# flowerfriend_rev1.net
KiCad netlist of a schematic drawn in EAGLE
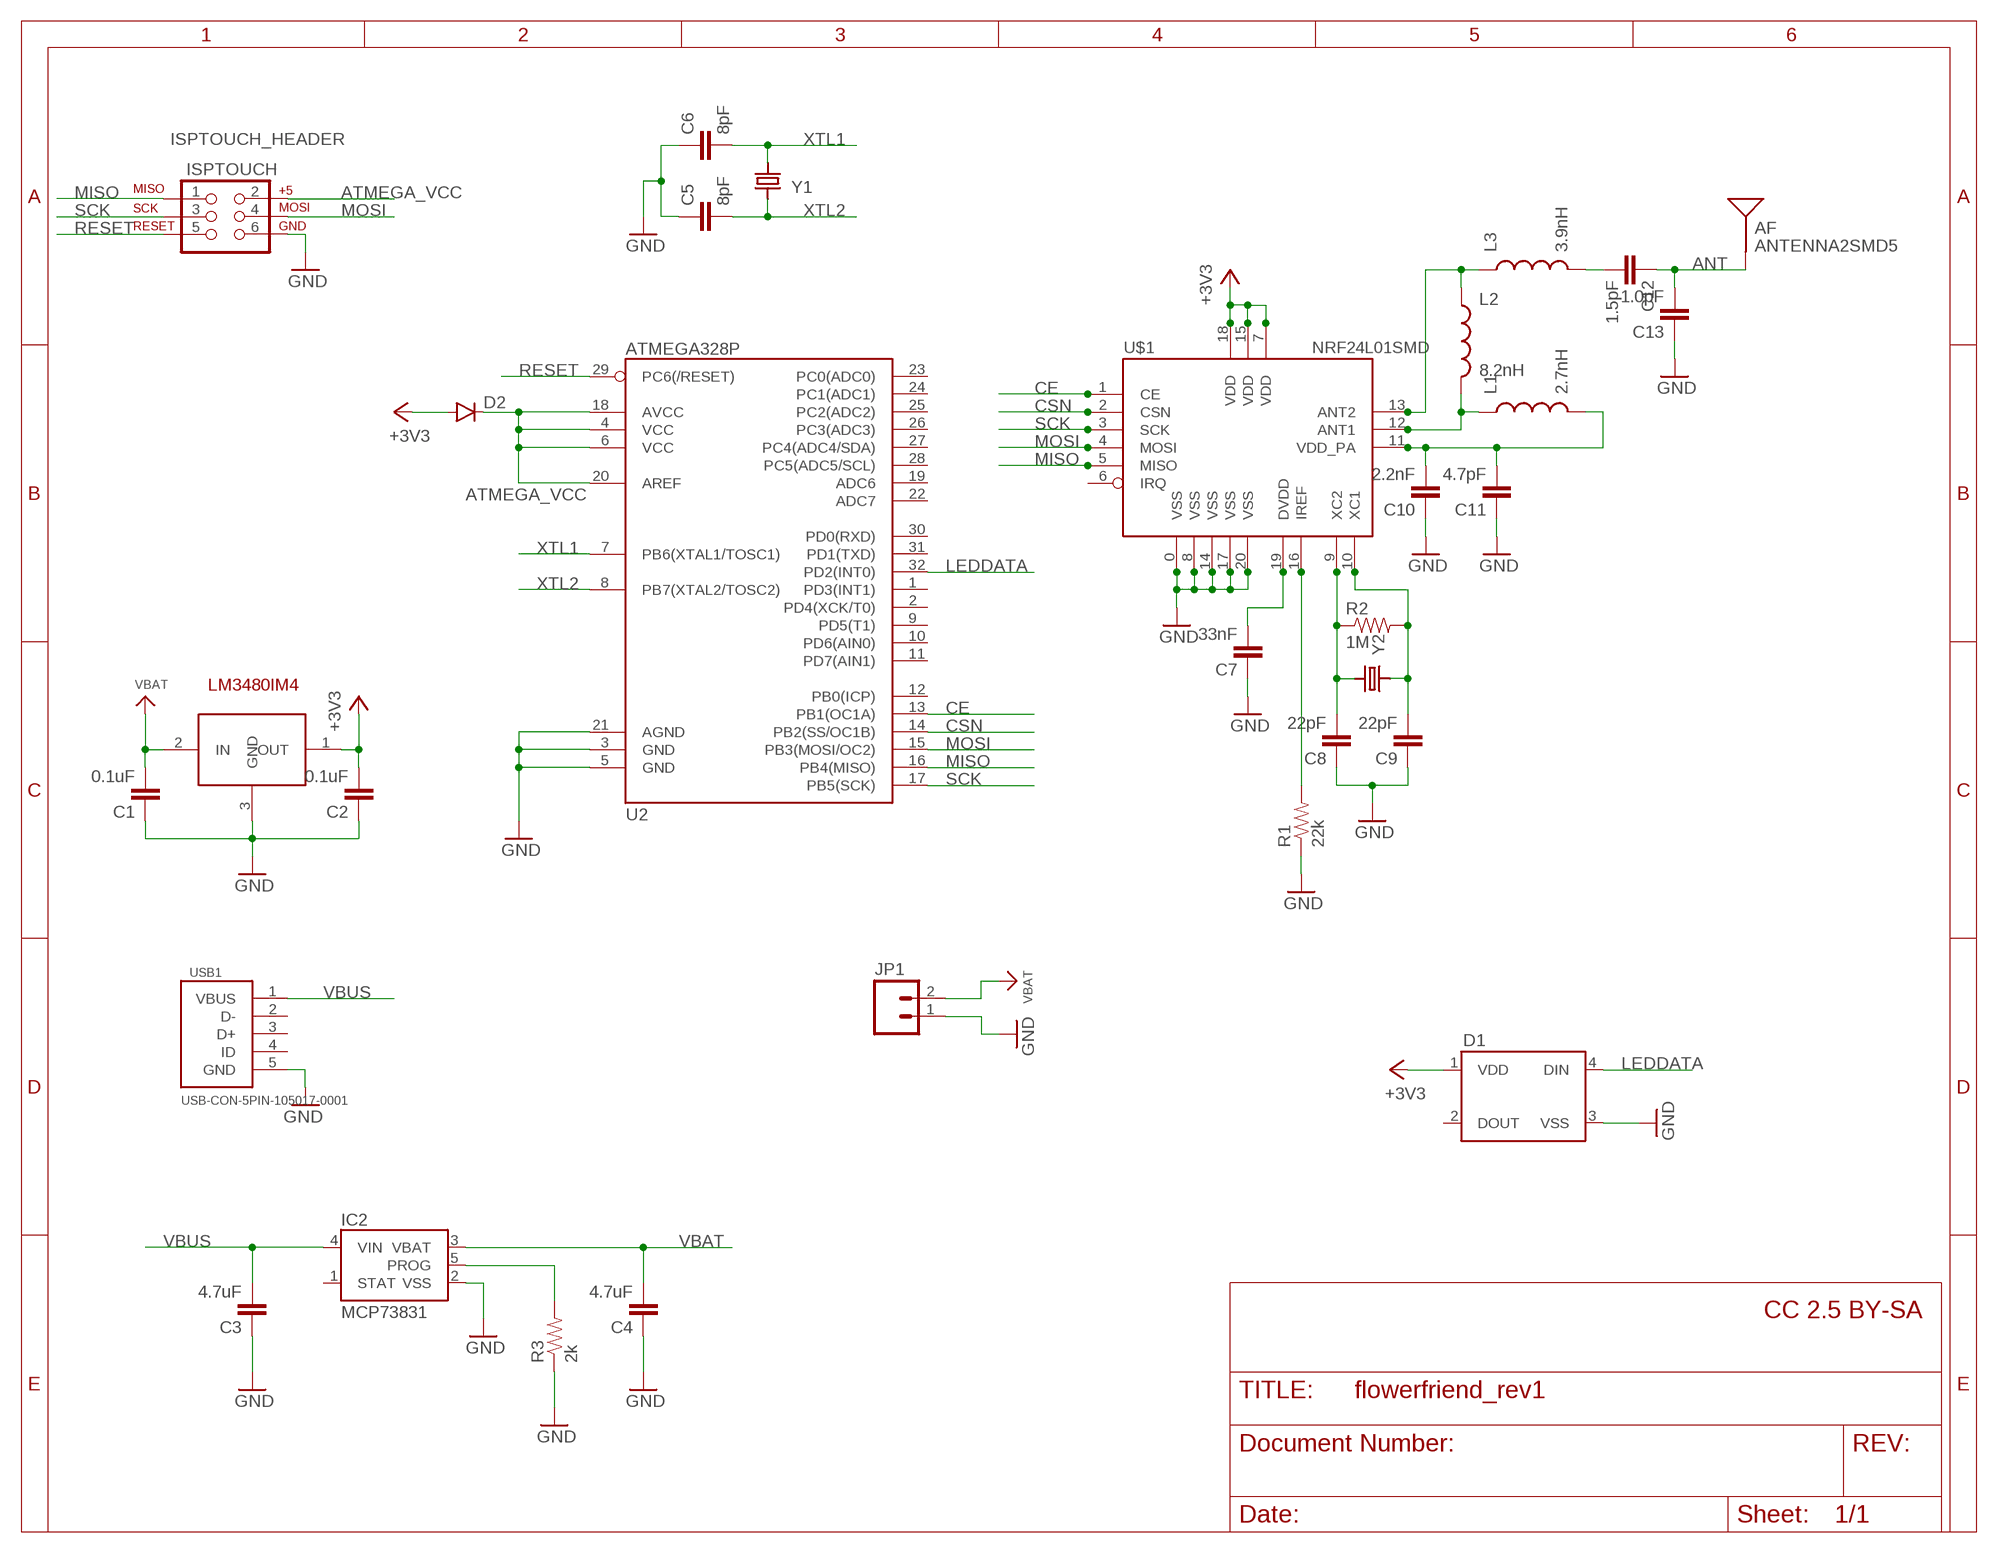
[diagram p0: schematic, sheet 1]

(export (version "E")
  (design (tool "Eeschema 10.0.6"))
  (components
    (comp (ref "AF")
      (value "ANTENNA2SMD5")
      (footprint "eagle-import:ANTENNA-CHIP5")
      (libsource (lib "eagle-import") (part "ANTENNA2SMD5"))
    )
    (comp (ref "C1")
      (value "0.1uF")
      (footprint "eagle-import:0805")
      (libsource (lib "eagle-import") (part "CAP0805"))
    )
    (comp (ref "C2")
      (value "0.1uF")
      (footprint "eagle-import:0805")
      (libsource (lib "eagle-import") (part "CAP0805"))
    )
    (comp (ref "C3")
      (value "4.7uF")
      (footprint "eagle-import:0805")
      (libsource (lib "eagle-import") (part "CAP0805"))
    )
    (comp (ref "C4")
      (value "4.7uF")
      (footprint "eagle-import:0805")
      (libsource (lib "eagle-import") (part "CAP0805"))
    )
    (comp (ref "C5")
      (value "8pF")
      (footprint "eagle-import:0805")
      (libsource (lib "eagle-import") (part "CAP0805"))
    )
    (comp (ref "C6")
      (value "8pF")
      (footprint "eagle-import:0805")
      (libsource (lib "eagle-import") (part "CAP0805"))
    )
    (comp (ref "C7")
      (value "33nF")
      (footprint "eagle-import:0805")
      (libsource (lib "eagle-import") (part "CAP0805"))
    )
    (comp (ref "C8")
      (value "22pF")
      (footprint "eagle-import:0805")
      (libsource (lib "eagle-import") (part "CAP0805"))
    )
    (comp (ref "C9")
      (value "22pF")
      (footprint "eagle-import:0805")
      (libsource (lib "eagle-import") (part "CAP0805"))
    )
    (comp (ref "C10")
      (value "2.2nF")
      (footprint "eagle-import:0805")
      (libsource (lib "eagle-import") (part "CAP0805"))
    )
    (comp (ref "C11")
      (value "4.7pF")
      (footprint "eagle-import:0805")
      (libsource (lib "eagle-import") (part "CAP0805"))
    )
    (comp (ref "C12")
      (value "1.5pF")
      (footprint "eagle-import:0805")
      (libsource (lib "eagle-import") (part "CAP0805"))
    )
    (comp (ref "C13")
      (value "1.0pF")
      (footprint "eagle-import:0805")
      (libsource (lib "eagle-import") (part "CAP0805"))
    )
    (comp (ref "D1")
      (value "WS2812B")
      (footprint "eagle-import:WS2812B")
      (libsource (lib "eagle-import") (part "WS2812B"))
    )
    (comp (ref "D2")
      (value "DIODESMA")
      (footprint "eagle-import:SMA-DIODE")
      (libsource (lib "eagle-import") (part "DIODESMA"))
    )
    (comp (ref "IC1")
      (value "LM3480IM4")
      (footprint "eagle-import:SOT23-3")
      (libsource (lib "eagle-import") (part "LM3480IM4"))
    )
    (comp (ref "IC2")
      (value "MCP73831")
      (footprint "eagle-import:SOT23-5")
      (libsource (lib "eagle-import") (part "MCP73831"))
    )
    (comp (ref "ISPTOUCH")
      (value "ISPTOUCH_HEADER")
      (footprint "eagle-import:AVX_9188_6-WAY_MATING_GUIDE")
      (libsource (lib "eagle-import") (part "ISPTOUCH_HEADER"))
    )
    (comp (ref "JP1")
      (value "M02PTH")
      (footprint "eagle-import:1X02")
      (libsource (lib "eagle-import") (part "M02PTH"))
    )
    (comp (ref "L1")
      (value "2.7nH")
      (footprint "eagle-import:0805")
      (libsource (lib "eagle-import") (part "INDUCTOR0805"))
    )
    (comp (ref "L2")
      (value "8.2nH")
      (footprint "eagle-import:0805")
      (libsource (lib "eagle-import") (part "INDUCTOR0805"))
    )
    (comp (ref "L3")
      (value "3.9nH")
      (footprint "eagle-import:0805")
      (libsource (lib "eagle-import") (part "INDUCTOR0805"))
    )
    (comp (ref "R1")
      (value "22k")
      (footprint "eagle-import:0805")
      (libsource (lib "eagle-import") (part "RESISTOR0805-RES"))
    )
    (comp (ref "R2")
      (value "1M")
      (footprint "eagle-import:0805")
      (libsource (lib "eagle-import") (part "RESISTOR0805-RES"))
    )
    (comp (ref "R3")
      (value "2k")
      (footprint "eagle-import:0805")
      (libsource (lib "eagle-import") (part "RESISTOR0805-RES"))
    )
    (comp (ref "U$1")
      (value "NRF24L01SMD")
      (footprint "eagle-import:QFN20")
      (libsource (lib "eagle-import") (part "NRF24L01SMD"))
    )
    (comp (ref "U2")
      (value "ATMEGA328P")
      (footprint "eagle-import:TQFP32-08")
      (libsource (lib "eagle-import") (part "ATMEGA328_SMT"))
    )
    (comp (ref "USB1")
      (value "USB-CON-5PIN-105017-0001")
      (footprint "eagle-import:USB-MICRO-MOLEX-105017-0001")
      (libsource (lib "eagle-import") (part "USB-CON-5PIN-105017-0001"))
    )
    (comp (ref "Y1")
      (value "16MHz")
      (footprint "eagle-import:NX5032GA")
      (libsource (lib "eagle-import") (part "CRYSTAL5X3.2"))
    )
    (comp (ref "Y2")
      (value "16MHz")
      (footprint "eagle-import:NX5032GA")
      (libsource (lib "eagle-import") (part "CRYSTAL5X3.2"))
    )
  )
  (nets
    (net (code "1") (name "+3V3") (class "Default")
      (node (ref "C2") (pin "2") (pinfunction "2_2") (pintype "passive"))
      (node (ref "D1") (pin "1") (pinfunction "VDD_1") (pintype "power_in"))
      (node (ref "D2") (pin "A") (pinfunction "A_A") (pintype "passive"))
      (node (ref "IC1") (pin "1") (pinfunction "OUT_1") (pintype "bidirectional"))
      (node (ref "U$1") (pin "15") (pinfunction "VDD_15") (pintype "power_in"))
      (node (ref "U$1") (pin "18") (pinfunction "VDD_18") (pintype "power_in"))
      (node (ref "U$1") (pin "7") (pinfunction "VDD_7") (pintype "power_in"))
    )
    (net (code "2") (name "/ANT") (class "Default")
      (node (ref "AF") (pin "FEED") (pinfunction "SIGNAL_FEED") (pintype "bidirectional"))
      (node (ref "C12") (pin "1") (pinfunction "1_1") (pintype "passive"))
      (node (ref "C13") (pin "2") (pinfunction "2_2") (pintype "passive"))
    )
    (net (code "3") (name "/ATMEGA_VCC") (class "Default")
      (node (ref "D2") (pin "C") (pinfunction "C_C") (pintype "passive"))
      (node (ref "ISPTOUCH") (pin "2") (pinfunction "2_2") (pintype "passive"))
      (node (ref "U2") (pin "18") (pinfunction "AVCC_18") (pintype "bidirectional"))
      (node (ref "U2") (pin "20") (pinfunction "AREF_20") (pintype "bidirectional"))
      (node (ref "U2") (pin "4") (pinfunction "VCC_4") (pintype "bidirectional"))
      (node (ref "U2") (pin "6") (pinfunction "VCC_6") (pintype "bidirectional"))
    )
    (net (code "4") (name "/CE") (class "Default")
      (node (ref "U$1") (pin "1") (pinfunction "CE_1") (pintype "input"))
      (node (ref "U2") (pin "13") (pinfunction "PB1(OC1A)_13") (pintype "bidirectional"))
    )
    (net (code "5") (name "/CSN") (class "Default")
      (node (ref "U$1") (pin "2") (pinfunction "CSN_2") (pintype "input"))
      (node (ref "U2") (pin "14") (pinfunction "PB2(SS/OC1B)_14") (pintype "bidirectional"))
    )
    (net (code "6") (name "/LEDDATA") (class "Default")
      (node (ref "D1") (pin "4") (pinfunction "DIN_4") (pintype "input"))
      (node (ref "U2") (pin "32") (pinfunction "PD2(INT0)_32") (pintype "bidirectional"))
    )
    (net (code "7") (name "/MISO") (class "Default")
      (node (ref "ISPTOUCH") (pin "1") (pinfunction "1_1") (pintype "passive"))
      (node (ref "U$1") (pin "5") (pinfunction "MISO_5") (pintype "output"))
      (node (ref "U2") (pin "16") (pinfunction "PB4(MISO)_16") (pintype "bidirectional"))
    )
    (net (code "8") (name "/MOSI") (class "Default")
      (node (ref "ISPTOUCH") (pin "4") (pinfunction "4_4") (pintype "passive"))
      (node (ref "U$1") (pin "4") (pinfunction "MOSI_4") (pintype "input"))
      (node (ref "U2") (pin "15") (pinfunction "PB3(MOSI/OC2)_15") (pintype "bidirectional"))
    )
    (net (code "9") (name "/RESET") (class "Default")
      (node (ref "ISPTOUCH") (pin "5") (pinfunction "5_5") (pintype "passive"))
      (node (ref "U2") (pin "29") (pinfunction "PC6(/RESET)_29") (pintype "bidirectional"))
    )
    (net (code "10") (name "/SCK") (class "Default")
      (node (ref "ISPTOUCH") (pin "3") (pinfunction "3_3") (pintype "passive"))
      (node (ref "U$1") (pin "3") (pinfunction "SCK_3") (pintype "input"))
      (node (ref "U2") (pin "17") (pinfunction "PB5(SCK)_17") (pintype "bidirectional"))
    )
    (net (code "11") (name "/VBUS") (class "Default")
      (node (ref "C3") (pin "2") (pinfunction "2_2") (pintype "passive"))
      (node (ref "IC2") (pin "4") (pinfunction "VIN_4") (pintype "power_in"))
      (node (ref "USB1") (pin "1") (pinfunction "VBUS_1") (pintype "power_in"))
    )
    (net (code "12") (name "/XTL1") (class "Default")
      (node (ref "C6") (pin "2") (pinfunction "2_2") (pintype "passive"))
      (node (ref "U2") (pin "7") (pinfunction "PB6(XTAL1/TOSC1)_7") (pintype "bidirectional"))
      (node (ref "Y1") (pin "P$2") (pinfunction "2_P$2") (pintype "passive"))
    )
    (net (code "13") (name "/XTL2") (class "Default")
      (node (ref "C5") (pin "2") (pinfunction "2_2") (pintype "passive"))
      (node (ref "U2") (pin "8") (pinfunction "PB7(XTAL2/TOSC2)_8") (pintype "bidirectional"))
      (node (ref "Y1") (pin "P$1") (pinfunction "1_P$1") (pintype "passive"))
    )
    (net (code "14") (name "GND") (class "Default")
      (node (ref "C1") (pin "1") (pinfunction "1_1") (pintype "passive"))
      (node (ref "C10") (pin "1") (pinfunction "1_1") (pintype "passive"))
      (node (ref "C11") (pin "1") (pinfunction "1_1") (pintype "passive"))
      (node (ref "C13") (pin "1") (pinfunction "1_1") (pintype "passive"))
      (node (ref "C2") (pin "1") (pinfunction "1_1") (pintype "passive"))
      (node (ref "C3") (pin "1") (pinfunction "1_1") (pintype "passive"))
      (node (ref "C4") (pin "1") (pinfunction "1_1") (pintype "passive"))
      (node (ref "C5") (pin "1") (pinfunction "1_1") (pintype "passive"))
      (node (ref "C6") (pin "1") (pinfunction "1_1") (pintype "passive"))
      (node (ref "C7") (pin "1") (pinfunction "1_1") (pintype "passive"))
      (node (ref "C8") (pin "1") (pinfunction "1_1") (pintype "passive"))
      (node (ref "C9") (pin "1") (pinfunction "1_1") (pintype "passive"))
      (node (ref "D1") (pin "3") (pinfunction "VSS_3") (pintype "power_in"))
      (node (ref "IC1") (pin "3") (pinfunction "GND_3") (pintype "bidirectional"))
      (node (ref "IC2") (pin "2") (pinfunction "VSS_2") (pintype "power_in"))
      (node (ref "ISPTOUCH") (pin "6") (pinfunction "6_6") (pintype "passive"))
      (node (ref "JP1") (pin "1") (pinfunction "1_1") (pintype "passive"))
      (node (ref "R1") (pin "1") (pinfunction "1_1") (pintype "passive"))
      (node (ref "R3") (pin "1") (pinfunction "1_1") (pintype "passive"))
      (node (ref "U$1") (pin "0") (pinfunction "VSS_0") (pintype "power_in"))
      (node (ref "U$1") (pin "14") (pinfunction "VSS_14") (pintype "power_in"))
      (node (ref "U$1") (pin "17") (pinfunction "VSS_17") (pintype "power_in"))
      (node (ref "U$1") (pin "20") (pinfunction "VSS_20") (pintype "power_in"))
      (node (ref "U$1") (pin "8") (pinfunction "VSS_8") (pintype "power_in"))
      (node (ref "U2") (pin "21") (pinfunction "AGND_21") (pintype "bidirectional"))
      (node (ref "U2") (pin "3") (pinfunction "GND_3") (pintype "bidirectional"))
      (node (ref "U2") (pin "5") (pinfunction "GND_5") (pintype "bidirectional"))
      (node (ref "USB1") (pin "5") (pinfunction "GND_5") (pintype "power_in"))
    )
    (net (code "15") (name "Net-(C12-Pad2)") (class "Default")
      (node (ref "C12") (pin "2") (pinfunction "2_2") (pintype "passive"))
      (node (ref "L3") (pin "2") (pinfunction "2_2") (pintype "passive"))
    )
    (net (code "16") (name "Net-(IC2-PROG)") (class "Default")
      (node (ref "IC2") (pin "5") (pinfunction "PROG_5") (pintype "input"))
      (node (ref "R3") (pin "2") (pinfunction "2_2") (pintype "passive"))
    )
    (net (code "17") (name "Net-(U$1-ANT1)") (class "Default")
      (node (ref "L1") (pin "1") (pinfunction "1_1") (pintype "passive"))
      (node (ref "L2") (pin "2") (pinfunction "2_2") (pintype "passive"))
      (node (ref "U$1") (pin "12") (pinfunction "ANT1_12") (pintype "output"))
    )
    (net (code "18") (name "Net-(U$1-ANT2)") (class "Default")
      (node (ref "L2") (pin "1") (pinfunction "1_1") (pintype "passive"))
      (node (ref "L3") (pin "1") (pinfunction "1_1") (pintype "passive"))
      (node (ref "U$1") (pin "13") (pinfunction "ANT2_13") (pintype "output"))
    )
    (net (code "19") (name "Net-(U$1-DVDD)") (class "Default")
      (node (ref "C7") (pin "2") (pinfunction "2_2") (pintype "passive"))
      (node (ref "U$1") (pin "19") (pinfunction "DVDD_19") (pintype "power_in"))
    )
    (net (code "20") (name "Net-(U$1-IREF)") (class "Default")
      (node (ref "R1") (pin "2") (pinfunction "2_2") (pintype "passive"))
      (node (ref "U$1") (pin "16") (pinfunction "IREF_16") (pintype "input"))
    )
    (net (code "21") (name "Net-(U$1-VDD_PA)") (class "Default")
      (node (ref "C10") (pin "2") (pinfunction "2_2") (pintype "passive"))
      (node (ref "C11") (pin "2") (pinfunction "2_2") (pintype "passive"))
      (node (ref "L1") (pin "2") (pinfunction "2_2") (pintype "passive"))
      (node (ref "U$1") (pin "11") (pinfunction "VDD_PA_11") (pintype "power_in"))
    )
    (net (code "22") (name "Net-(U$1-XC1)") (class "Default")
      (node (ref "C9") (pin "2") (pinfunction "2_2") (pintype "passive"))
      (node (ref "R2") (pin "2") (pinfunction "2_2") (pintype "passive"))
      (node (ref "U$1") (pin "10") (pinfunction "XC1_10") (pintype "input"))
      (node (ref "Y2") (pin "P$1") (pinfunction "1_P$1") (pintype "passive"))
    )
    (net (code "23") (name "Net-(U$1-XC2)") (class "Default")
      (node (ref "C8") (pin "2") (pinfunction "2_2") (pintype "passive"))
      (node (ref "R2") (pin "1") (pinfunction "1_1") (pintype "passive"))
      (node (ref "U$1") (pin "9") (pinfunction "XC2_9") (pintype "input"))
      (node (ref "Y2") (pin "P$2") (pinfunction "2_P$2") (pintype "passive"))
    )
    (net (code "24") (name "VBAT") (class "Default")
      (node (ref "C1") (pin "2") (pinfunction "2_2") (pintype "passive"))
      (node (ref "C4") (pin "2") (pinfunction "2_2") (pintype "passive"))
      (node (ref "IC1") (pin "2") (pinfunction "IN_2") (pintype "bidirectional"))
      (node (ref "IC2") (pin "3") (pinfunction "VBAT_3") (pintype "power_in"))
      (node (ref "JP1") (pin "2") (pinfunction "2_2") (pintype "passive"))
    )
    (net (code "25") (name "unconnected-(D1-DOUT-Pad2)") (class "Default")
      (node (ref "D1") (pin "2") (pinfunction "DOUT_2") (pintype "output"))
    )
    (net (code "26") (name "unconnected-(IC2-STAT-Pad1)") (class "Default")
      (node (ref "IC2") (pin "1") (pinfunction "STAT_1") (pintype "output"))
    )
    (net (code "27") (name "unconnected-(U$1-IRQ-Pad6)") (class "Default")
      (node (ref "U$1") (pin "6") (pinfunction "IRQ_6") (pintype "output"))
    )
    (net (code "28") (name "unconnected-(U2-ADC6-Pad19)") (class "Default")
      (node (ref "U2") (pin "19") (pinfunction "ADC6_19") (pintype "bidirectional"))
    )
    (net (code "29") (name "unconnected-(U2-ADC7-Pad22)") (class "Default")
      (node (ref "U2") (pin "22") (pinfunction "ADC7_22") (pintype "bidirectional"))
    )
    (net (code "30") (name "unconnected-(U2-PB0(ICP)-Pad12)") (class "Default")
      (node (ref "U2") (pin "12") (pinfunction "PB0(ICP)_12") (pintype "bidirectional"))
    )
    (net (code "31") (name "unconnected-(U2-PC0(ADC0)-Pad23)") (class "Default")
      (node (ref "U2") (pin "23") (pinfunction "PC0(ADC0)_23") (pintype "bidirectional"))
    )
    (net (code "32") (name "unconnected-(U2-PC1(ADC1)-Pad24)") (class "Default")
      (node (ref "U2") (pin "24") (pinfunction "PC1(ADC1)_24") (pintype "bidirectional"))
    )
    (net (code "33") (name "unconnected-(U2-PC2(ADC2)-Pad25)") (class "Default")
      (node (ref "U2") (pin "25") (pinfunction "PC2(ADC2)_25") (pintype "bidirectional"))
    )
    (net (code "34") (name "unconnected-(U2-PC3(ADC3)-Pad26)") (class "Default")
      (node (ref "U2") (pin "26") (pinfunction "PC3(ADC3)_26") (pintype "bidirectional"))
    )
    (net (code "35") (name "unconnected-(U2-PC4(ADC4{slash}SDA)-Pad27)") (class "Default")
      (node (ref "U2") (pin "27") (pinfunction "PC4(ADC4/SDA)_27") (pintype "bidirectional"))
    )
    (net (code "36") (name "unconnected-(U2-PC5(ADC5{slash}SCL)-Pad28)") (class "Default")
      (node (ref "U2") (pin "28") (pinfunction "PC5(ADC5/SCL)_28") (pintype "bidirectional"))
    )
    (net (code "37") (name "unconnected-(U2-PD0(RXD)-Pad30)") (class "Default")
      (node (ref "U2") (pin "30") (pinfunction "PD0(RXD)_30") (pintype "bidirectional"))
    )
    (net (code "38") (name "unconnected-(U2-PD1(TXD)-Pad31)") (class "Default")
      (node (ref "U2") (pin "31") (pinfunction "PD1(TXD)_31") (pintype "bidirectional"))
    )
    (net (code "39") (name "unconnected-(U2-PD3(INT1)-Pad1)") (class "Default")
      (node (ref "U2") (pin "1") (pinfunction "PD3(INT1)_1") (pintype "bidirectional"))
    )
    (net (code "40") (name "unconnected-(U2-PD4(XCK{slash}T0)-Pad2)") (class "Default")
      (node (ref "U2") (pin "2") (pinfunction "PD4(XCK/T0)_2") (pintype "bidirectional"))
    )
    (net (code "41") (name "unconnected-(U2-PD5(T1)-Pad9)") (class "Default")
      (node (ref "U2") (pin "9") (pinfunction "PD5(T1)_9") (pintype "bidirectional"))
    )
    (net (code "42") (name "unconnected-(U2-PD6(AIN0)-Pad10)") (class "Default")
      (node (ref "U2") (pin "10") (pinfunction "PD6(AIN0)_10") (pintype "bidirectional"))
    )
    (net (code "43") (name "unconnected-(U2-PD7(AIN1)-Pad11)") (class "Default")
      (node (ref "U2") (pin "11") (pinfunction "PD7(AIN1)_11") (pintype "bidirectional"))
    )
    (net (code "44") (name "unconnected-(USB1-D+-Pad3)") (class "Default")
      (node (ref "USB1") (pin "3") (pinfunction "D+_3") (pintype "bidirectional"))
    )
    (net (code "45") (name "unconnected-(USB1-D--Pad2)") (class "Default")
      (node (ref "USB1") (pin "2") (pinfunction "D-_2") (pintype "bidirectional"))
    )
    (net (code "46") (name "unconnected-(USB1-ID-Pad4)") (class "Default")
      (node (ref "USB1") (pin "4") (pinfunction "ID_4") (pintype "bidirectional"))
    )
  )
)
